# maddomat-slave.net
KiCad netlist of a schematic drawn in EAGLE
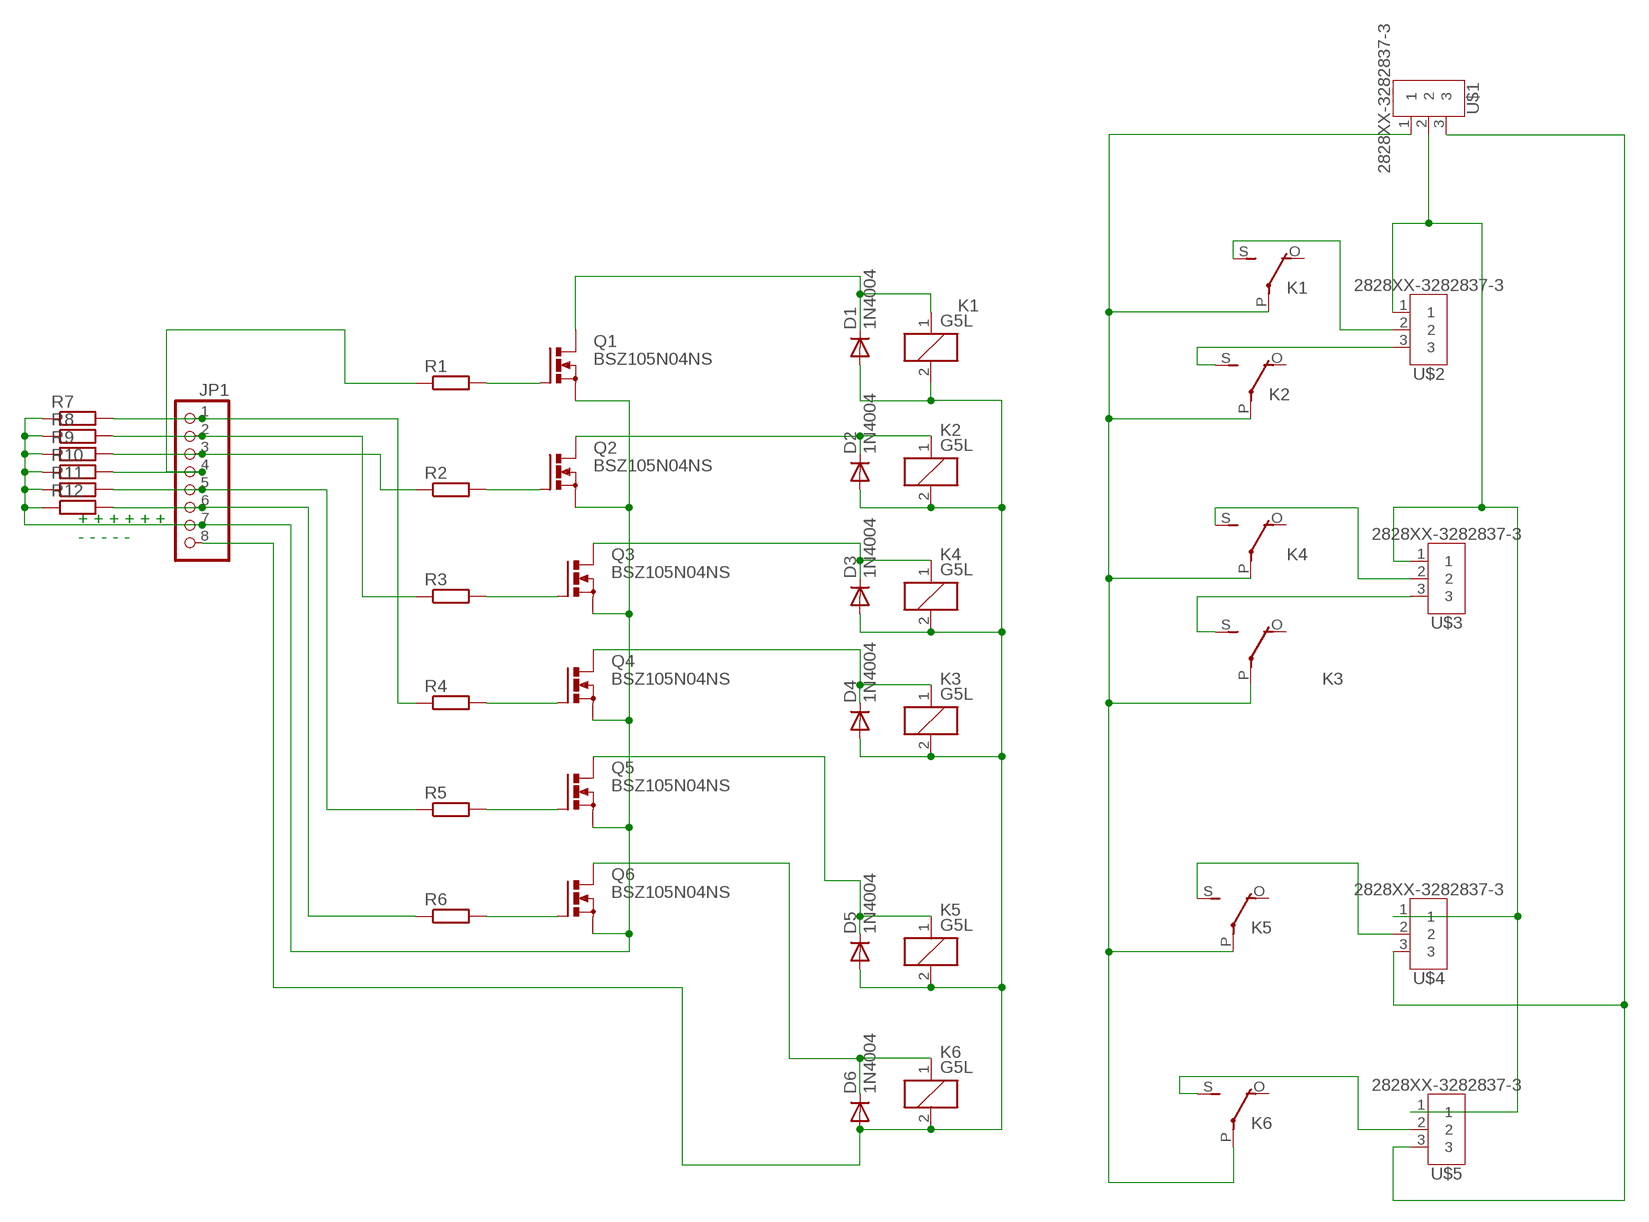
[diagram p0: schematic, sheet 1]

(export (version "E")
  (design (tool "Eeschema 10.0.6"))
  (components
    (comp (ref "D1")
      (value "1N4004")
      (footprint "eagle-import:DO41-10")
      (libsource (lib "eagle-import") (part "1N4004"))
    )
    (comp (ref "D2")
      (value "1N4004")
      (footprint "eagle-import:DO41-10")
      (libsource (lib "eagle-import") (part "1N4004"))
    )
    (comp (ref "D3")
      (value "1N4004")
      (footprint "eagle-import:DO41-10")
      (libsource (lib "eagle-import") (part "1N4004"))
    )
    (comp (ref "D4")
      (value "1N4004")
      (footprint "eagle-import:DO41-10")
      (libsource (lib "eagle-import") (part "1N4004"))
    )
    (comp (ref "D5")
      (value "1N4004")
      (footprint "eagle-import:DO41-10")
      (libsource (lib "eagle-import") (part "1N4004"))
    )
    (comp (ref "D6")
      (value "1N4004")
      (footprint "eagle-import:DO41-10")
      (libsource (lib "eagle-import") (part "1N4004"))
    )
    (comp (ref "JP1")
      (value "PINHD-1X8")
      (footprint "eagle-import:1X08")
      (libsource (lib "eagle-import") (part "PINHD-1X8"))
    )
    (comp (ref "K1")
      (value "G5L")
      (footprint "eagle-import:G5LE")
      (libsource (lib "eagle-import") (part "G5L"))
    )
    (comp (ref "K2")
      (value "G5L")
      (footprint "eagle-import:G5LE")
      (libsource (lib "eagle-import") (part "G5L"))
    )
    (comp (ref "K3")
      (value "G5L")
      (footprint "eagle-import:G5LE")
      (libsource (lib "eagle-import") (part "G5L"))
    )
    (comp (ref "K4")
      (value "G5L")
      (footprint "eagle-import:G5LE")
      (libsource (lib "eagle-import") (part "G5L"))
    )
    (comp (ref "K5")
      (value "G5L")
      (footprint "eagle-import:G5LE")
      (libsource (lib "eagle-import") (part "G5L"))
    )
    (comp (ref "K6")
      (value "G5L")
      (footprint "eagle-import:G5LE")
      (libsource (lib "eagle-import") (part "G5L"))
    )
    (comp (ref "Q1")
      (value "BSZ105N04NS")
      (footprint "eagle-import:PG-TDSON-8")
      (libsource (lib "eagle-import") (part "BSZ105N04NS"))
    )
    (comp (ref "Q2")
      (value "BSZ105N04NS")
      (footprint "eagle-import:PG-TDSON-8")
      (libsource (lib "eagle-import") (part "BSZ105N04NS"))
    )
    (comp (ref "Q3")
      (value "BSZ105N04NS")
      (footprint "eagle-import:PG-TDSON-8")
      (libsource (lib "eagle-import") (part "BSZ105N04NS"))
    )
    (comp (ref "Q4")
      (value "BSZ105N04NS")
      (footprint "eagle-import:PG-TDSON-8")
      (libsource (lib "eagle-import") (part "BSZ105N04NS"))
    )
    (comp (ref "Q5")
      (value "BSZ105N04NS")
      (footprint "eagle-import:PG-TDSON-8")
      (libsource (lib "eagle-import") (part "BSZ105N04NS"))
    )
    (comp (ref "Q6")
      (value "BSZ105N04NS")
      (footprint "eagle-import:PG-TDSON-8")
      (libsource (lib "eagle-import") (part "BSZ105N04NS"))
    )
    (comp (ref "R1")
      (value "R-EU_M0805")
      (footprint "eagle-import:M0805")
      (libsource (lib "eagle-import") (part "R-EU_M0805"))
    )
    (comp (ref "R2")
      (value "R-EU_M0805")
      (footprint "eagle-import:M0805")
      (libsource (lib "eagle-import") (part "R-EU_M0805"))
    )
    (comp (ref "R3")
      (value "R-EU_M0805")
      (footprint "eagle-import:M0805")
      (libsource (lib "eagle-import") (part "R-EU_M0805"))
    )
    (comp (ref "R4")
      (value "R-EU_M0805")
      (footprint "eagle-import:M0805")
      (libsource (lib "eagle-import") (part "R-EU_M0805"))
    )
    (comp (ref "R5")
      (value "R-EU_M0805")
      (footprint "eagle-import:M0805")
      (libsource (lib "eagle-import") (part "R-EU_M0805"))
    )
    (comp (ref "R6")
      (value "R-EU_M0805")
      (footprint "eagle-import:M0805")
      (libsource (lib "eagle-import") (part "R-EU_M0805"))
    )
    (comp (ref "R7")
      (value "R-EU_M0805")
      (footprint "eagle-import:M0805")
      (libsource (lib "eagle-import") (part "R-EU_M0805"))
    )
    (comp (ref "R8")
      (value "R-EU_M0805")
      (footprint "eagle-import:M0805")
      (libsource (lib "eagle-import") (part "R-EU_M0805"))
    )
    (comp (ref "R9")
      (value "R-EU_M0805")
      (footprint "eagle-import:M0805")
      (libsource (lib "eagle-import") (part "R-EU_M0805"))
    )
    (comp (ref "R10")
      (value "R-EU_M0805")
      (footprint "eagle-import:M0805")
      (libsource (lib "eagle-import") (part "R-EU_M0805"))
    )
    (comp (ref "R11")
      (value "R-EU_M0805")
      (footprint "eagle-import:M0805")
      (libsource (lib "eagle-import") (part "R-EU_M0805"))
    )
    (comp (ref "R12")
      (value "R-EU_M0805")
      (footprint "eagle-import:M0805")
      (libsource (lib "eagle-import") (part "R-EU_M0805"))
    )
    (comp (ref "U$1")
      (value "2828XX-3282837-3")
      (footprint "eagle-import:TERMBLK_508-3N")
      (fields (field (name "MANUFACTURER") "TE Connectivity") (field (name "MPN") "282837-3"))
      (libsource (lib "eagle-import") (part "2828XX-3282837-3"))
    )
    (comp (ref "U$2")
      (value "2828XX-3282837-3")
      (footprint "eagle-import:TERMBLK_508-3N")
      (fields (field (name "MANUFACTURER") "TE Connectivity") (field (name "MPN") "282837-3"))
      (libsource (lib "eagle-import") (part "2828XX-3282837-3"))
    )
    (comp (ref "U$3")
      (value "2828XX-3282837-3")
      (footprint "eagle-import:TERMBLK_508-3N")
      (fields (field (name "MANUFACTURER") "TE Connectivity") (field (name "MPN") "282837-3"))
      (libsource (lib "eagle-import") (part "2828XX-3282837-3"))
    )
    (comp (ref "U$4")
      (value "2828XX-3282837-3")
      (footprint "eagle-import:TERMBLK_508-3N")
      (fields (field (name "MANUFACTURER") "TE Connectivity") (field (name "MPN") "282837-3"))
      (libsource (lib "eagle-import") (part "2828XX-3282837-3"))
    )
    (comp (ref "U$5")
      (value "2828XX-3282837-3")
      (footprint "eagle-import:TERMBLK_508-3N")
      (fields (field (name "MANUFACTURER") "TE Connectivity") (field (name "MPN") "282837-3"))
      (libsource (lib "eagle-import") (part "2828XX-3282837-3"))
    )
  )
  (nets
    (net (code "1") (name "Net-(D1-PadA)") (class "Default")
      (node (ref "D1") (pin "A") (pinfunction "A_A") (pintype "passive"))
      (node (ref "D2") (pin "A") (pinfunction "A_A") (pintype "passive"))
      (node (ref "D3") (pin "A") (pinfunction "A_A") (pintype "passive"))
      (node (ref "D4") (pin "A") (pinfunction "A_A") (pintype "passive"))
      (node (ref "D5") (pin "A") (pinfunction "A_A") (pintype "passive"))
      (node (ref "D6") (pin "A") (pinfunction "A_A") (pintype "passive"))
      (node (ref "JP1") (pin "8") (pinfunction "8_8") (pintype "passive"))
      (node (ref "K1") (pin "2") (pinfunction "2_2") (pintype "passive"))
      (node (ref "K2") (pin "2") (pinfunction "2_2") (pintype "passive"))
      (node (ref "K3") (pin "2") (pinfunction "2_2") (pintype "passive"))
      (node (ref "K4") (pin "2") (pinfunction "2_2") (pintype "passive"))
      (node (ref "K5") (pin "2") (pinfunction "2_2") (pintype "passive"))
      (node (ref "K6") (pin "2") (pinfunction "2_2") (pintype "passive"))
    )
    (net (code "2") (name "Net-(D1-PadC)") (class "Default")
      (node (ref "D1") (pin "C") (pinfunction "C_C") (pintype "passive"))
      (node (ref "K1") (pin "1") (pinfunction "1_1") (pintype "passive"))
      (node (ref "Q1") (pin "5") (pinfunction "D_5") (pintype "passive"))
      (node (ref "Q1") (pin "6") (pinfunction "D_6") (pintype "passive"))
      (node (ref "Q1") (pin "7") (pinfunction "D_7") (pintype "passive"))
      (node (ref "Q1") (pin "8") (pinfunction "D_8") (pintype "passive"))
      (node (ref "Q1") (pin "TH") (pinfunction "D_TH") (pintype "passive"))
    )
    (net (code "3") (name "Net-(D2-PadC)") (class "Default")
      (node (ref "D2") (pin "C") (pinfunction "C_C") (pintype "passive"))
      (node (ref "K2") (pin "1") (pinfunction "1_1") (pintype "passive"))
      (node (ref "Q2") (pin "5") (pinfunction "D_5") (pintype "passive"))
      (node (ref "Q2") (pin "6") (pinfunction "D_6") (pintype "passive"))
      (node (ref "Q2") (pin "7") (pinfunction "D_7") (pintype "passive"))
      (node (ref "Q2") (pin "8") (pinfunction "D_8") (pintype "passive"))
      (node (ref "Q2") (pin "TH") (pinfunction "D_TH") (pintype "passive"))
    )
    (net (code "4") (name "Net-(D3-PadC)") (class "Default")
      (node (ref "D3") (pin "C") (pinfunction "C_C") (pintype "passive"))
      (node (ref "K4") (pin "1") (pinfunction "1_1") (pintype "passive"))
      (node (ref "Q3") (pin "5") (pinfunction "D_5") (pintype "passive"))
      (node (ref "Q3") (pin "6") (pinfunction "D_6") (pintype "passive"))
      (node (ref "Q3") (pin "7") (pinfunction "D_7") (pintype "passive"))
      (node (ref "Q3") (pin "8") (pinfunction "D_8") (pintype "passive"))
      (node (ref "Q3") (pin "TH") (pinfunction "D_TH") (pintype "passive"))
    )
    (net (code "5") (name "Net-(D4-PadC)") (class "Default")
      (node (ref "D4") (pin "C") (pinfunction "C_C") (pintype "passive"))
      (node (ref "K3") (pin "1") (pinfunction "1_1") (pintype "passive"))
      (node (ref "Q4") (pin "5") (pinfunction "D_5") (pintype "passive"))
      (node (ref "Q4") (pin "6") (pinfunction "D_6") (pintype "passive"))
      (node (ref "Q4") (pin "7") (pinfunction "D_7") (pintype "passive"))
      (node (ref "Q4") (pin "8") (pinfunction "D_8") (pintype "passive"))
      (node (ref "Q4") (pin "TH") (pinfunction "D_TH") (pintype "passive"))
    )
    (net (code "6") (name "Net-(D5-PadC)") (class "Default")
      (node (ref "D5") (pin "C") (pinfunction "C_C") (pintype "passive"))
      (node (ref "K5") (pin "1") (pinfunction "1_1") (pintype "passive"))
      (node (ref "Q5") (pin "5") (pinfunction "D_5") (pintype "passive"))
      (node (ref "Q5") (pin "6") (pinfunction "D_6") (pintype "passive"))
      (node (ref "Q5") (pin "7") (pinfunction "D_7") (pintype "passive"))
      (node (ref "Q5") (pin "8") (pinfunction "D_8") (pintype "passive"))
      (node (ref "Q5") (pin "TH") (pinfunction "D_TH") (pintype "passive"))
    )
    (net (code "7") (name "Net-(D6-PadC)") (class "Default")
      (node (ref "D6") (pin "C") (pinfunction "C_C") (pintype "passive"))
      (node (ref "K6") (pin "1") (pinfunction "1_1") (pintype "passive"))
      (node (ref "Q6") (pin "5") (pinfunction "D_5") (pintype "passive"))
      (node (ref "Q6") (pin "6") (pinfunction "D_6") (pintype "passive"))
      (node (ref "Q6") (pin "7") (pinfunction "D_7") (pintype "passive"))
      (node (ref "Q6") (pin "8") (pinfunction "D_8") (pintype "passive"))
      (node (ref "Q6") (pin "TH") (pinfunction "D_TH") (pintype "passive"))
    )
    (net (code "8") (name "Net-(JP1-Pad1)") (class "Default")
      (node (ref "JP1") (pin "1") (pinfunction "1_1") (pintype "passive"))
      (node (ref "R4") (pin "1") (pinfunction "1_1") (pintype "passive"))
      (node (ref "R7") (pin "2") (pinfunction "2_2") (pintype "passive"))
    )
    (net (code "9") (name "Net-(JP1-Pad2)") (class "Default")
      (node (ref "JP1") (pin "2") (pinfunction "2_2") (pintype "passive"))
      (node (ref "R3") (pin "1") (pinfunction "1_1") (pintype "passive"))
      (node (ref "R8") (pin "2") (pinfunction "2_2") (pintype "passive"))
    )
    (net (code "10") (name "Net-(JP1-Pad3)") (class "Default")
      (node (ref "JP1") (pin "3") (pinfunction "3_3") (pintype "passive"))
      (node (ref "R2") (pin "1") (pinfunction "1_1") (pintype "passive"))
      (node (ref "R9") (pin "2") (pinfunction "2_2") (pintype "passive"))
    )
    (net (code "11") (name "Net-(JP1-Pad4)") (class "Default")
      (node (ref "JP1") (pin "4") (pinfunction "4_4") (pintype "passive"))
      (node (ref "R1") (pin "1") (pinfunction "1_1") (pintype "passive"))
      (node (ref "R10") (pin "2") (pinfunction "2_2") (pintype "passive"))
    )
    (net (code "12") (name "Net-(JP1-Pad5)") (class "Default")
      (node (ref "JP1") (pin "5") (pinfunction "5_5") (pintype "passive"))
      (node (ref "R11") (pin "2") (pinfunction "2_2") (pintype "passive"))
      (node (ref "R5") (pin "1") (pinfunction "1_1") (pintype "passive"))
    )
    (net (code "13") (name "Net-(JP1-Pad6)") (class "Default")
      (node (ref "JP1") (pin "6") (pinfunction "6_6") (pintype "passive"))
      (node (ref "R12") (pin "2") (pinfunction "2_2") (pintype "passive"))
      (node (ref "R6") (pin "1") (pinfunction "1_1") (pintype "passive"))
    )
    (net (code "14") (name "Net-(JP1-Pad7)") (class "Default")
      (node (ref "JP1") (pin "7") (pinfunction "7_7") (pintype "passive"))
      (node (ref "Q1") (pin "1") (pinfunction "S_1") (pintype "passive"))
      (node (ref "Q1") (pin "2") (pinfunction "S_2") (pintype "passive"))
      (node (ref "Q1") (pin "3") (pinfunction "S_3") (pintype "passive"))
      (node (ref "Q2") (pin "1") (pinfunction "S_1") (pintype "passive"))
      (node (ref "Q2") (pin "2") (pinfunction "S_2") (pintype "passive"))
      (node (ref "Q2") (pin "3") (pinfunction "S_3") (pintype "passive"))
      (node (ref "Q3") (pin "1") (pinfunction "S_1") (pintype "passive"))
      (node (ref "Q3") (pin "2") (pinfunction "S_2") (pintype "passive"))
      (node (ref "Q3") (pin "3") (pinfunction "S_3") (pintype "passive"))
      (node (ref "Q4") (pin "1") (pinfunction "S_1") (pintype "passive"))
      (node (ref "Q4") (pin "2") (pinfunction "S_2") (pintype "passive"))
      (node (ref "Q4") (pin "3") (pinfunction "S_3") (pintype "passive"))
      (node (ref "Q5") (pin "1") (pinfunction "S_1") (pintype "passive"))
      (node (ref "Q5") (pin "2") (pinfunction "S_2") (pintype "passive"))
      (node (ref "Q5") (pin "3") (pinfunction "S_3") (pintype "passive"))
      (node (ref "Q6") (pin "1") (pinfunction "S_1") (pintype "passive"))
      (node (ref "Q6") (pin "2") (pinfunction "S_2") (pintype "passive"))
      (node (ref "Q6") (pin "3") (pinfunction "S_3") (pintype "passive"))
      (node (ref "R10") (pin "1") (pinfunction "1_1") (pintype "passive"))
      (node (ref "R11") (pin "1") (pinfunction "1_1") (pintype "passive"))
      (node (ref "R12") (pin "1") (pinfunction "1_1") (pintype "passive"))
      (node (ref "R7") (pin "1") (pinfunction "1_1") (pintype "passive"))
      (node (ref "R8") (pin "1") (pinfunction "1_1") (pintype "passive"))
      (node (ref "R9") (pin "1") (pinfunction "1_1") (pintype "passive"))
    )
    (net (code "15") (name "Net-(K1-PadP)") (class "Default")
      (node (ref "K1") (pin "P") (pinfunction "P_P") (pintype "passive"))
      (node (ref "K2") (pin "P") (pinfunction "P_P") (pintype "passive"))
      (node (ref "K3") (pin "P") (pinfunction "P_P") (pintype "passive"))
      (node (ref "K4") (pin "P") (pinfunction "P_P") (pintype "passive"))
      (node (ref "K5") (pin "P") (pinfunction "P_P") (pintype "passive"))
      (node (ref "K6") (pin "P") (pinfunction "P_P") (pintype "passive"))
      (node (ref "U$1") (pin "1") (pinfunction "1_1") (pintype "bidirectional"))
    )
    (net (code "16") (name "Net-(K1-PadS)") (class "Default")
      (node (ref "K1") (pin "S") (pinfunction "S_S") (pintype "passive"))
      (node (ref "U$2") (pin "2") (pinfunction "2_2") (pintype "bidirectional"))
    )
    (net (code "17") (name "Net-(K2-PadS)") (class "Default")
      (node (ref "K2") (pin "S") (pinfunction "S_S") (pintype "passive"))
      (node (ref "U$2") (pin "3") (pinfunction "3_3") (pintype "bidirectional"))
    )
    (net (code "18") (name "Net-(K3-PadS)") (class "Default")
      (node (ref "K3") (pin "S") (pinfunction "S_S") (pintype "passive"))
      (node (ref "U$3") (pin "3") (pinfunction "3_3") (pintype "bidirectional"))
    )
    (net (code "19") (name "Net-(K4-PadS)") (class "Default")
      (node (ref "K4") (pin "S") (pinfunction "S_S") (pintype "passive"))
      (node (ref "U$3") (pin "2") (pinfunction "2_2") (pintype "bidirectional"))
    )
    (net (code "20") (name "Net-(K5-PadS)") (class "Default")
      (node (ref "K5") (pin "S") (pinfunction "S_S") (pintype "passive"))
      (node (ref "U$4") (pin "2") (pinfunction "2_2") (pintype "bidirectional"))
    )
    (net (code "21") (name "Net-(K6-PadS)") (class "Default")
      (node (ref "K6") (pin "S") (pinfunction "S_S") (pintype "passive"))
      (node (ref "U$5") (pin "2") (pinfunction "2_2") (pintype "bidirectional"))
    )
    (net (code "22") (name "Net-(Q1-G)") (class "Default")
      (node (ref "Q1") (pin "4") (pinfunction "G_4") (pintype "passive"))
      (node (ref "R1") (pin "2") (pinfunction "2_2") (pintype "passive"))
    )
    (net (code "23") (name "Net-(Q2-G)") (class "Default")
      (node (ref "Q2") (pin "4") (pinfunction "G_4") (pintype "passive"))
      (node (ref "R2") (pin "2") (pinfunction "2_2") (pintype "passive"))
    )
    (net (code "24") (name "Net-(Q3-G)") (class "Default")
      (node (ref "Q3") (pin "4") (pinfunction "G_4") (pintype "passive"))
      (node (ref "R3") (pin "2") (pinfunction "2_2") (pintype "passive"))
    )
    (net (code "25") (name "Net-(Q4-G)") (class "Default")
      (node (ref "Q4") (pin "4") (pinfunction "G_4") (pintype "passive"))
      (node (ref "R4") (pin "2") (pinfunction "2_2") (pintype "passive"))
    )
    (net (code "26") (name "Net-(Q5-G)") (class "Default")
      (node (ref "Q5") (pin "4") (pinfunction "G_4") (pintype "passive"))
      (node (ref "R5") (pin "2") (pinfunction "2_2") (pintype "passive"))
    )
    (net (code "27") (name "Net-(Q6-G)") (class "Default")
      (node (ref "Q6") (pin "4") (pinfunction "G_4") (pintype "passive"))
      (node (ref "R6") (pin "2") (pinfunction "2_2") (pintype "passive"))
    )
    (net (code "28") (name "Net-(U$1-Pad2)") (class "Default")
      (node (ref "U$1") (pin "2") (pinfunction "2_2") (pintype "bidirectional"))
      (node (ref "U$2") (pin "1") (pinfunction "1_1") (pintype "bidirectional"))
      (node (ref "U$3") (pin "1") (pinfunction "1_1") (pintype "bidirectional"))
      (node (ref "U$4") (pin "1") (pinfunction "1_1") (pintype "bidirectional"))
      (node (ref "U$5") (pin "1") (pinfunction "1_1") (pintype "bidirectional"))
    )
    (net (code "29") (name "Net-(U$1-Pad3)") (class "Default")
      (node (ref "U$1") (pin "3") (pinfunction "3_3") (pintype "bidirectional"))
      (node (ref "U$4") (pin "3") (pinfunction "3_3") (pintype "bidirectional"))
      (node (ref "U$5") (pin "3") (pinfunction "3_3") (pintype "bidirectional"))
    )
    (net (code "30") (name "unconnected-(K1-PadO)") (class "Default")
      (node (ref "K1") (pin "O") (pinfunction "O_O") (pintype "passive"))
    )
    (net (code "31") (name "unconnected-(K2-PadO)") (class "Default")
      (node (ref "K2") (pin "O") (pinfunction "O_O") (pintype "passive"))
    )
    (net (code "32") (name "unconnected-(K3-PadO)") (class "Default")
      (node (ref "K3") (pin "O") (pinfunction "O_O") (pintype "passive"))
    )
    (net (code "33") (name "unconnected-(K4-PadO)") (class "Default")
      (node (ref "K4") (pin "O") (pinfunction "O_O") (pintype "passive"))
    )
    (net (code "34") (name "unconnected-(K5-PadO)") (class "Default")
      (node (ref "K5") (pin "O") (pinfunction "O_O") (pintype "passive"))
    )
    (net (code "35") (name "unconnected-(K6-PadO)") (class "Default")
      (node (ref "K6") (pin "O") (pinfunction "O_O") (pintype "passive"))
    )
  )
)
